# expansion.net
KiCad netlist of a schematic drawn in Altium Designer
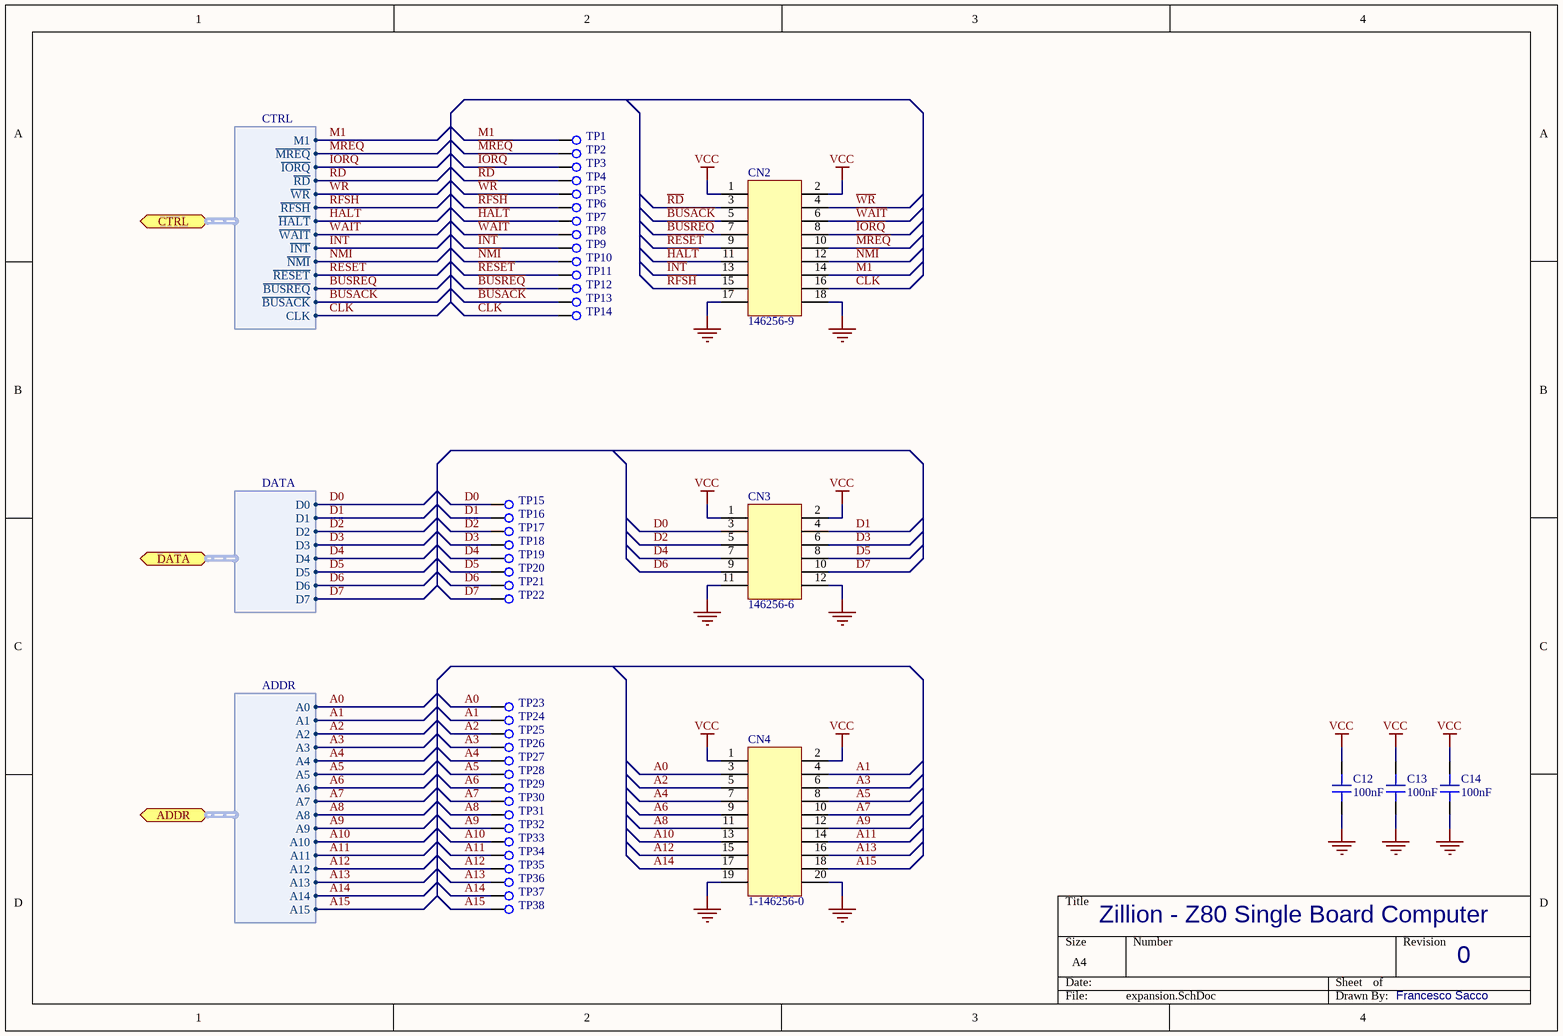
[diagram p0: expansion.SchDoc]

(export (version "E")
  (design (tool "Eeschema 10.0.6"))
  (components
    (comp (ref "C12")
      (value "100nF")
      (footprint "DiskCapacitor")
      (description "Capacitor")
      (libsource (lib "Basic") (part "Capacitor"))
    )
    (comp (ref "C13")
      (value "100nF")
      (footprint "DiskCapacitor")
      (description "Capacitor")
      (libsource (lib "Basic") (part "Capacitor"))
    )
    (comp (ref "C14")
      (value "100nF")
      (footprint "DiskCapacitor")
      (description "Capacitor")
      (libsource (lib "Basic") (part "Capacitor"))
    )
    (comp (ref "CN2")
      (value "146256-9")
      (footprint "146256-9")
      (description "CONN Header Breakaway")
      (libsource (lib "TE Connectivity") (part "146256-9"))
    )
    (comp (ref "CN3")
      (value "146256-6")
      (footprint "146256-6")
      (description "CONN Header Breakaway")
      (libsource (lib "TE Connectivity") (part "146256-6"))
    )
    (comp (ref "CN4")
      (value "1-146256-0")
      (footprint "1-146256-0")
      (description "CONN Header Breakaway")
      (libsource (lib "TE Connectivity") (part "1-146256-0"))
    )
    (comp (ref "TP1")
      (value "Test Point")
      (footprint "Test Point Trace")
      (libsource (lib "Basic") (part "Test Point"))
    )
    (comp (ref "TP2")
      (value "Test Point")
      (footprint "Test Point Trace")
      (libsource (lib "Basic") (part "Test Point"))
    )
    (comp (ref "TP3")
      (value "Test Point")
      (footprint "Test Point Trace")
      (libsource (lib "Basic") (part "Test Point"))
    )
    (comp (ref "TP4")
      (value "Test Point")
      (footprint "Test Point Trace")
      (libsource (lib "Basic") (part "Test Point"))
    )
    (comp (ref "TP5")
      (value "Test Point")
      (footprint "Test Point Trace")
      (libsource (lib "Basic") (part "Test Point"))
    )
    (comp (ref "TP6")
      (value "Test Point")
      (footprint "Test Point Trace")
      (libsource (lib "Basic") (part "Test Point"))
    )
    (comp (ref "TP7")
      (value "Test Point")
      (footprint "Test Point Trace")
      (libsource (lib "Basic") (part "Test Point"))
    )
    (comp (ref "TP8")
      (value "Test Point")
      (footprint "Test Point Trace")
      (libsource (lib "Basic") (part "Test Point"))
    )
    (comp (ref "TP9")
      (value "Test Point")
      (footprint "Test Point Trace")
      (libsource (lib "Basic") (part "Test Point"))
    )
    (comp (ref "TP10")
      (value "Test Point")
      (footprint "Test Point Trace")
      (libsource (lib "Basic") (part "Test Point"))
    )
    (comp (ref "TP11")
      (value "Test Point")
      (footprint "Test Point Trace")
      (libsource (lib "Basic") (part "Test Point"))
    )
    (comp (ref "TP12")
      (value "Test Point")
      (footprint "Test Point Trace")
      (libsource (lib "Basic") (part "Test Point"))
    )
    (comp (ref "TP13")
      (value "Test Point")
      (footprint "Test Point Trace")
      (libsource (lib "Basic") (part "Test Point"))
    )
    (comp (ref "TP14")
      (value "Test Point")
      (footprint "Test Point Trace")
      (libsource (lib "Basic") (part "Test Point"))
    )
    (comp (ref "TP15")
      (value "Test Point")
      (footprint "Test Point Trace")
      (libsource (lib "Basic") (part "Test Point"))
    )
    (comp (ref "TP16")
      (value "Test Point")
      (footprint "Test Point Trace")
      (libsource (lib "Basic") (part "Test Point"))
    )
    (comp (ref "TP17")
      (value "Test Point")
      (footprint "Test Point Trace")
      (libsource (lib "Basic") (part "Test Point"))
    )
    (comp (ref "TP18")
      (value "Test Point")
      (footprint "Test Point Trace")
      (libsource (lib "Basic") (part "Test Point"))
    )
    (comp (ref "TP19")
      (value "Test Point")
      (footprint "Test Point Trace")
      (libsource (lib "Basic") (part "Test Point"))
    )
    (comp (ref "TP20")
      (value "Test Point")
      (footprint "Test Point Trace")
      (libsource (lib "Basic") (part "Test Point"))
    )
    (comp (ref "TP21")
      (value "Test Point")
      (footprint "Test Point Trace")
      (libsource (lib "Basic") (part "Test Point"))
    )
    (comp (ref "TP22")
      (value "Test Point")
      (footprint "Test Point Trace")
      (libsource (lib "Basic") (part "Test Point"))
    )
    (comp (ref "TP23")
      (value "Test Point")
      (footprint "Test Point Trace")
      (libsource (lib "Basic") (part "Test Point"))
    )
    (comp (ref "TP24")
      (value "Test Point")
      (footprint "Test Point Trace")
      (libsource (lib "Basic") (part "Test Point"))
    )
    (comp (ref "TP25")
      (value "Test Point")
      (footprint "Test Point Trace")
      (libsource (lib "Basic") (part "Test Point"))
    )
    (comp (ref "TP26")
      (value "Test Point")
      (footprint "Test Point Trace")
      (libsource (lib "Basic") (part "Test Point"))
    )
    (comp (ref "TP27")
      (value "Test Point")
      (footprint "Test Point Trace")
      (libsource (lib "Basic") (part "Test Point"))
    )
    (comp (ref "TP28")
      (value "Test Point")
      (footprint "Test Point Trace")
      (libsource (lib "Basic") (part "Test Point"))
    )
    (comp (ref "TP29")
      (value "Test Point")
      (footprint "Test Point Trace")
      (libsource (lib "Basic") (part "Test Point"))
    )
    (comp (ref "TP30")
      (value "Test Point")
      (footprint "Test Point Trace")
      (libsource (lib "Basic") (part "Test Point"))
    )
    (comp (ref "TP31")
      (value "Test Point")
      (footprint "Test Point Trace")
      (libsource (lib "Basic") (part "Test Point"))
    )
    (comp (ref "TP32")
      (value "Test Point")
      (footprint "Test Point Trace")
      (libsource (lib "Basic") (part "Test Point"))
    )
    (comp (ref "TP33")
      (value "Test Point")
      (footprint "Test Point Trace")
      (libsource (lib "Basic") (part "Test Point"))
    )
    (comp (ref "TP34")
      (value "Test Point")
      (footprint "Test Point Trace")
      (libsource (lib "Basic") (part "Test Point"))
    )
    (comp (ref "TP35")
      (value "Test Point")
      (footprint "Test Point Trace")
      (libsource (lib "Basic") (part "Test Point"))
    )
    (comp (ref "TP36")
      (value "Test Point")
      (footprint "Test Point Trace")
      (libsource (lib "Basic") (part "Test Point"))
    )
    (comp (ref "TP37")
      (value "Test Point")
      (footprint "Test Point Trace")
      (libsource (lib "Basic") (part "Test Point"))
    )
    (comp (ref "TP38")
      (value "Test Point")
      (footprint "Test Point Trace")
      (libsource (lib "Basic") (part "Test Point"))
    )
  )
  (nets
    (net (code "4") (name "/A0") (class "Default")
      (node (ref "CN4") (pin "3") (pinfunction "3_3") (pintype "passive"))
      (node (ref "TP23") (pin "1") (pinfunction "1_1") (pintype "passive"))
    )
    (net (code "5") (name "/A1") (class "Default")
      (node (ref "CN4") (pin "4") (pinfunction "4_4") (pintype "passive"))
      (node (ref "TP24") (pin "1") (pinfunction "1_1") (pintype "passive"))
    )
    (net (code "6") (name "/A2") (class "Default")
      (node (ref "CN4") (pin "5") (pinfunction "5_5") (pintype "passive"))
      (node (ref "TP25") (pin "1") (pinfunction "1_1") (pintype "passive"))
    )
    (net (code "7") (name "/A3") (class "Default")
      (node (ref "CN4") (pin "6") (pinfunction "6_6") (pintype "passive"))
      (node (ref "TP26") (pin "1") (pinfunction "1_1") (pintype "passive"))
    )
    (net (code "8") (name "/A4") (class "Default")
      (node (ref "CN4") (pin "7") (pinfunction "7_7") (pintype "passive"))
      (node (ref "TP27") (pin "1") (pinfunction "1_1") (pintype "passive"))
    )
    (net (code "9") (name "/A5") (class "Default")
      (node (ref "CN4") (pin "8") (pinfunction "8_8") (pintype "passive"))
      (node (ref "TP28") (pin "1") (pinfunction "1_1") (pintype "passive"))
    )
    (net (code "10") (name "/A6") (class "Default")
      (node (ref "CN4") (pin "9") (pinfunction "9_9") (pintype "passive"))
      (node (ref "TP29") (pin "1") (pinfunction "1_1") (pintype "passive"))
    )
    (net (code "11") (name "/A7") (class "Default")
      (node (ref "CN4") (pin "10") (pinfunction "10_10") (pintype "passive"))
      (node (ref "TP30") (pin "1") (pinfunction "1_1") (pintype "passive"))
    )
    (net (code "12") (name "/A8") (class "Default")
      (node (ref "CN4") (pin "11") (pinfunction "11_11") (pintype "passive"))
      (node (ref "TP31") (pin "1") (pinfunction "1_1") (pintype "passive"))
    )
    (net (code "13") (name "/A9") (class "Default")
      (node (ref "CN4") (pin "12") (pinfunction "12_12") (pintype "passive"))
      (node (ref "TP32") (pin "1") (pinfunction "1_1") (pintype "passive"))
    )
    (net (code "14") (name "/A10") (class "Default")
      (node (ref "CN4") (pin "13") (pinfunction "13_13") (pintype "passive"))
      (node (ref "TP33") (pin "1") (pinfunction "1_1") (pintype "passive"))
    )
    (net (code "15") (name "/A11") (class "Default")
      (node (ref "CN4") (pin "14") (pinfunction "14_14") (pintype "passive"))
      (node (ref "TP34") (pin "1") (pinfunction "1_1") (pintype "passive"))
    )
    (net (code "16") (name "/A12") (class "Default")
      (node (ref "CN4") (pin "15") (pinfunction "15_15") (pintype "passive"))
      (node (ref "TP35") (pin "1") (pinfunction "1_1") (pintype "passive"))
    )
    (net (code "17") (name "/A13") (class "Default")
      (node (ref "CN4") (pin "16") (pinfunction "16_16") (pintype "passive"))
      (node (ref "TP36") (pin "1") (pinfunction "1_1") (pintype "passive"))
    )
    (net (code "18") (name "/A14") (class "Default")
      (node (ref "CN4") (pin "17") (pinfunction "17_17") (pintype "passive"))
      (node (ref "TP37") (pin "1") (pinfunction "1_1") (pintype "passive"))
    )
    (net (code "19") (name "/A15") (class "Default")
      (node (ref "CN4") (pin "18") (pinfunction "18_18") (pintype "passive"))
      (node (ref "TP38") (pin "1") (pinfunction "1_1") (pintype "passive"))
    )
    (net (code "20") (name "/CLK") (class "Default")
      (node (ref "CN2") (pin "16") (pinfunction "16_16") (pintype "passive"))
      (node (ref "TP14") (pin "1") (pinfunction "1_1") (pintype "passive"))
    )
    (net (code "21") (name "/D0") (class "Default")
      (node (ref "CN3") (pin "3") (pinfunction "3_3") (pintype "passive"))
      (node (ref "TP15") (pin "1") (pinfunction "1_1") (pintype "passive"))
    )
    (net (code "22") (name "/D1") (class "Default")
      (node (ref "CN3") (pin "4") (pinfunction "4_4") (pintype "passive"))
      (node (ref "TP16") (pin "1") (pinfunction "1_1") (pintype "passive"))
    )
    (net (code "23") (name "/D2") (class "Default")
      (node (ref "CN3") (pin "5") (pinfunction "5_5") (pintype "passive"))
      (node (ref "TP17") (pin "1") (pinfunction "1_1") (pintype "passive"))
    )
    (net (code "24") (name "/D3") (class "Default")
      (node (ref "CN3") (pin "6") (pinfunction "6_6") (pintype "passive"))
      (node (ref "TP18") (pin "1") (pinfunction "1_1") (pintype "passive"))
    )
    (net (code "25") (name "/D4") (class "Default")
      (node (ref "CN3") (pin "7") (pinfunction "7_7") (pintype "passive"))
      (node (ref "TP19") (pin "1") (pinfunction "1_1") (pintype "passive"))
    )
    (net (code "26") (name "/D5") (class "Default")
      (node (ref "CN3") (pin "8") (pinfunction "8_8") (pintype "passive"))
      (node (ref "TP20") (pin "1") (pinfunction "1_1") (pintype "passive"))
    )
    (net (code "27") (name "/D6") (class "Default")
      (node (ref "CN3") (pin "9") (pinfunction "9_9") (pintype "passive"))
      (node (ref "TP21") (pin "1") (pinfunction "1_1") (pintype "passive"))
    )
    (net (code "28") (name "/D7") (class "Default")
      (node (ref "CN3") (pin "10") (pinfunction "10_10") (pintype "passive"))
      (node (ref "TP22") (pin "1") (pinfunction "1_1") (pintype "passive"))
    )
    (net (code "29") (name "/M1") (class "Default")
      (node (ref "CN2") (pin "14") (pinfunction "14_14") (pintype "passive"))
      (node (ref "TP1") (pin "1") (pinfunction "1_1") (pintype "passive"))
    )
    (net (code "33") (name "/~{BUSACK}") (class "Default")
      (node (ref "CN2") (pin "5") (pinfunction "5_5") (pintype "passive"))
      (node (ref "TP13") (pin "1") (pinfunction "1_1") (pintype "passive"))
    )
    (net (code "34") (name "/~{BUSREQ}") (class "Default")
      (node (ref "CN2") (pin "7") (pinfunction "7_7") (pintype "passive"))
      (node (ref "TP12") (pin "1") (pinfunction "1_1") (pintype "passive"))
    )
    (net (code "35") (name "/~{HALT}") (class "Default")
      (node (ref "CN2") (pin "11") (pinfunction "11_11") (pintype "passive"))
      (node (ref "TP7") (pin "1") (pinfunction "1_1") (pintype "passive"))
    )
    (net (code "36") (name "/~{INT}") (class "Default")
      (node (ref "CN2") (pin "13") (pinfunction "13_13") (pintype "passive"))
      (node (ref "TP9") (pin "1") (pinfunction "1_1") (pintype "passive"))
    )
    (net (code "37") (name "/~{IORQ}") (class "Default")
      (node (ref "CN2") (pin "8") (pinfunction "8_8") (pintype "passive"))
      (node (ref "TP3") (pin "1") (pinfunction "1_1") (pintype "passive"))
    )
    (net (code "38") (name "/~{MREQ}") (class "Default")
      (node (ref "CN2") (pin "10") (pinfunction "10_10") (pintype "passive"))
      (node (ref "TP2") (pin "1") (pinfunction "1_1") (pintype "passive"))
    )
    (net (code "39") (name "/~{NMI}") (class "Default")
      (node (ref "CN2") (pin "12") (pinfunction "12_12") (pintype "passive"))
      (node (ref "TP10") (pin "1") (pinfunction "1_1") (pintype "passive"))
    )
    (net (code "40") (name "/~{RD}") (class "Default")
      (node (ref "CN2") (pin "3") (pinfunction "3_3") (pintype "passive"))
      (node (ref "TP4") (pin "1") (pinfunction "1_1") (pintype "passive"))
    )
    (net (code "41") (name "/~{RESET}") (class "Default")
      (node (ref "CN2") (pin "9") (pinfunction "9_9") (pintype "passive"))
      (node (ref "TP11") (pin "1") (pinfunction "1_1") (pintype "passive"))
    )
    (net (code "42") (name "/~{RFSH}") (class "Default")
      (node (ref "CN2") (pin "15") (pinfunction "15_15") (pintype "passive"))
      (node (ref "TP6") (pin "1") (pinfunction "1_1") (pintype "passive"))
    )
    (net (code "43") (name "/~{WAIT}") (class "Default")
      (node (ref "CN2") (pin "6") (pinfunction "6_6") (pintype "passive"))
      (node (ref "TP8") (pin "1") (pinfunction "1_1") (pintype "passive"))
    )
    (net (code "44") (name "/~{WR}") (class "Default")
      (node (ref "CN2") (pin "4") (pinfunction "4_4") (pintype "passive"))
      (node (ref "TP5") (pin "1") (pinfunction "1_1") (pintype "passive"))
    )
    (net (code "45") (name "GND") (class "Default")
      (node (ref "C12") (pin "1") (pinfunction "1_1") (pintype "passive"))
      (node (ref "C13") (pin "1") (pinfunction "1_1") (pintype "passive"))
      (node (ref "C14") (pin "1") (pinfunction "1_1") (pintype "passive"))
      (node (ref "CN2") (pin "17") (pinfunction "17_17") (pintype "passive"))
      (node (ref "CN2") (pin "18") (pinfunction "18_18") (pintype "passive"))
      (node (ref "CN3") (pin "11") (pinfunction "11_11") (pintype "passive"))
      (node (ref "CN3") (pin "12") (pinfunction "12_12") (pintype "passive"))
      (node (ref "CN4") (pin "19") (pinfunction "19_19") (pintype "passive"))
      (node (ref "CN4") (pin "20") (pinfunction "20_20") (pintype "passive"))
    )
    (net (code "46") (name "VCC") (class "Default")
      (node (ref "C12") (pin "2") (pinfunction "2_2") (pintype "passive"))
      (node (ref "C13") (pin "2") (pinfunction "2_2") (pintype "passive"))
      (node (ref "C14") (pin "2") (pinfunction "2_2") (pintype "passive"))
      (node (ref "CN2") (pin "1") (pinfunction "1_1") (pintype "passive"))
      (node (ref "CN2") (pin "2") (pinfunction "2_2") (pintype "passive"))
      (node (ref "CN3") (pin "1") (pinfunction "1_1") (pintype "passive"))
      (node (ref "CN3") (pin "2") (pinfunction "2_2") (pintype "passive"))
      (node (ref "CN4") (pin "1") (pinfunction "1_1") (pintype "passive"))
      (node (ref "CN4") (pin "2") (pinfunction "2_2") (pintype "passive"))
    )
  )
)
